# Vin_Buck_Module.net
KiCad netlist of a schematic drawn in EAGLE
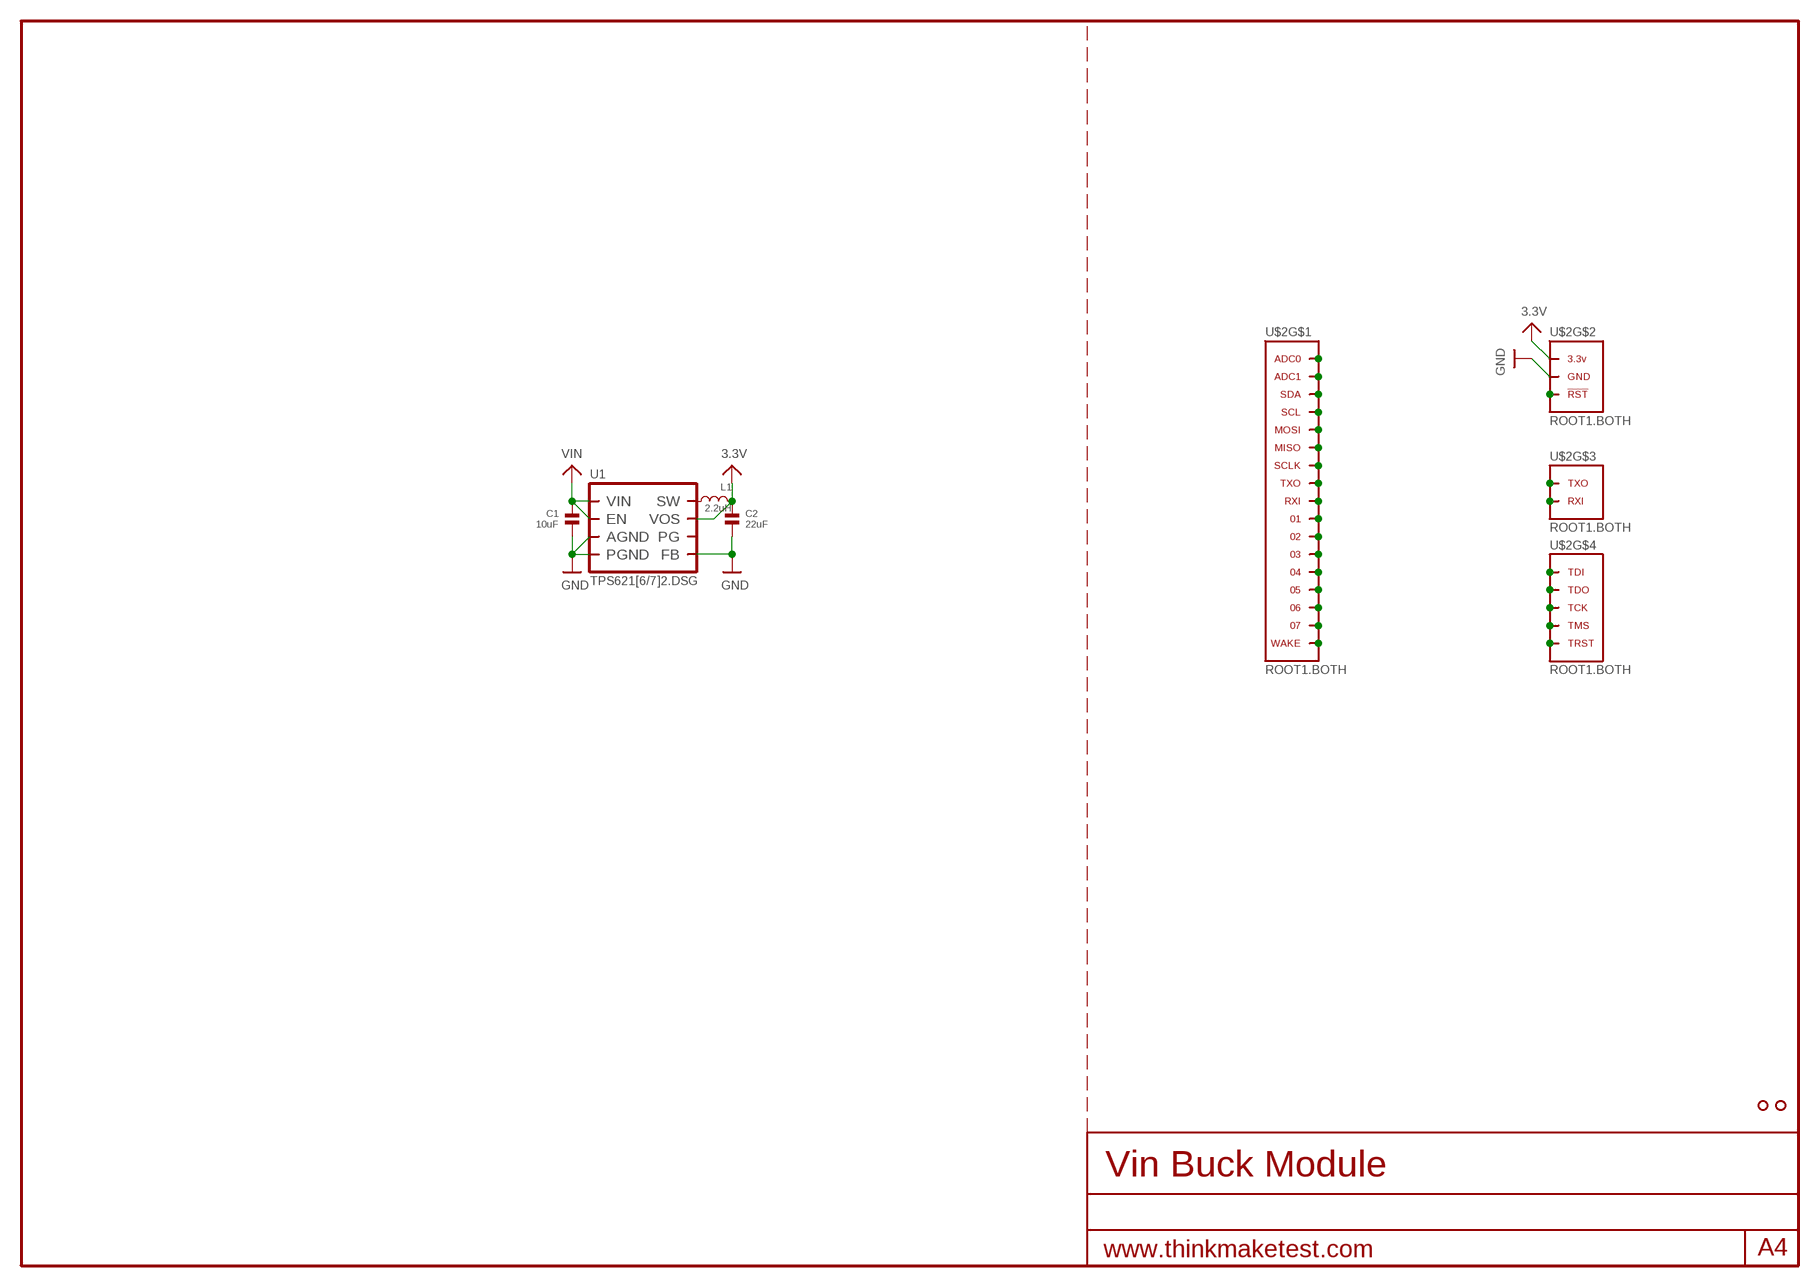
[diagram p0: schematic, sheet 1]

(export (version "E")
  (design (tool "Eeschema 10.0.6"))
  (components
    (comp (ref "C1")
      (value "10uF")
      (footprint "eagle-import:0805")
      (libsource (lib "eagle-import") (part "CAPACITOR.0805"))
    )
    (comp (ref "C2")
      (value "22uF")
      (footprint "eagle-import:0805")
      (libsource (lib "eagle-import") (part "CAPACITOR.0805"))
    )
    (comp (ref "L1")
      (value "2.2uH")
      (footprint "eagle-import:SDR0403")
      (libsource (lib "eagle-import") (part "INDUCTOR-SDR0403"))
    )
    (comp (ref "U$2")
      (value "ROOT1.BOTH")
      (footprint "eagle-import:ROOT1.BOTH")
      (libsource (lib "eagle-import") (part "ROOT1.BOTH"))
    )
    (comp (ref "U$3")
      (value "HOLE.#2")
      (footprint "eagle-import:#2")
      (libsource (lib "eagle-import") (part "HOLE.#2"))
    )
    (comp (ref "U$4")
      (value "HOLE.#2")
      (footprint "eagle-import:#2")
      (libsource (lib "eagle-import") (part "HOLE.#2"))
    )
    (comp (ref "U1")
      (value "TPS621[6/7]2.DSG")
      (footprint "eagle-import:DSG")
      (libsource (lib "eagle-import") (part "TPS621[6/7]2.DSG"))
    )
  )
  (nets
    (net (code "1") (name "3.3V") (class "Default")
      (node (ref "C2") (pin "1") (pinfunction "1_1") (pintype "bidirectional"))
      (node (ref "L1") (pin "1") (pinfunction "1_1") (pintype "passive"))
      (node (ref "U$2") (pin "3.3V@1") (pinfunction "3.3V_3.3V@1") (pintype "bidirectional"))
      (node (ref "U$2") (pin "3.3V@10") (pinfunction "3.3V_3.3V@10") (pintype "bidirectional"))
      (node (ref "U$2") (pin "3.3V@11") (pinfunction "3.3V_3.3V@11") (pintype "bidirectional"))
      (node (ref "U$2") (pin "3.3V@12") (pinfunction "3.3V_3.3V@12") (pintype "bidirectional"))
      (node (ref "U$2") (pin "3.3V@13") (pinfunction "3.3V_3.3V@13") (pintype "bidirectional"))
      (node (ref "U$2") (pin "3.3V@14") (pinfunction "3.3V_3.3V@14") (pintype "bidirectional"))
      (node (ref "U$2") (pin "3.3V@15") (pinfunction "3.3V_3.3V@15") (pintype "bidirectional"))
      (node (ref "U$2") (pin "3.3V@16") (pinfunction "3.3V_3.3V@16") (pintype "bidirectional"))
      (node (ref "U$2") (pin "3.3V@17") (pinfunction "3.3V_3.3V@17") (pintype "bidirectional"))
      (node (ref "U$2") (pin "3.3V@18") (pinfunction "3.3V_3.3V@18") (pintype "bidirectional"))
      (node (ref "U$2") (pin "3.3V@19") (pinfunction "3.3V_3.3V@19") (pintype "bidirectional"))
      (node (ref "U$2") (pin "3.3V@2") (pinfunction "3.3V_3.3V@2") (pintype "bidirectional"))
      (node (ref "U$2") (pin "3.3V@20") (pinfunction "3.3V_3.3V@20") (pintype "bidirectional"))
      (node (ref "U$2") (pin "3.3V@21") (pinfunction "3.3V_3.3V@21") (pintype "bidirectional"))
      (node (ref "U$2") (pin "3.3V@22") (pinfunction "3.3V_3.3V@22") (pintype "bidirectional"))
      (node (ref "U$2") (pin "3.3V@23") (pinfunction "3.3V_3.3V@23") (pintype "bidirectional"))
      (node (ref "U$2") (pin "3.3V@24") (pinfunction "3.3V_3.3V@24") (pintype "bidirectional"))
      (node (ref "U$2") (pin "3.3V@3") (pinfunction "3.3V_3.3V@3") (pintype "bidirectional"))
      (node (ref "U$2") (pin "3.3V@4") (pinfunction "3.3V_3.3V@4") (pintype "bidirectional"))
      (node (ref "U$2") (pin "3.3V@5") (pinfunction "3.3V_3.3V@5") (pintype "bidirectional"))
      (node (ref "U$2") (pin "3.3V@6") (pinfunction "3.3V_3.3V@6") (pintype "bidirectional"))
      (node (ref "U$2") (pin "3.3V@7") (pinfunction "3.3V_3.3V@7") (pintype "bidirectional"))
      (node (ref "U$2") (pin "3.3V@8") (pinfunction "3.3V_3.3V@8") (pintype "bidirectional"))
      (node (ref "U$2") (pin "3.3V@9") (pinfunction "3.3V_3.3V@9") (pintype "bidirectional"))
      (node (ref "U$2") (pin "3.3V@VIA") (pinfunction "3.3V_3.3V@VIA") (pintype "bidirectional"))
      (node (ref "U1") (pin "6") (pinfunction "VOS_6") (pintype "bidirectional"))
    )
    (net (code "2") (name "GND") (class "Default")
      (node (ref "C1") (pin "2") (pinfunction "2_2") (pintype "bidirectional"))
      (node (ref "C2") (pin "2") (pinfunction "2_2") (pintype "bidirectional"))
      (node (ref "U$2") (pin "GND@1") (pinfunction "GND_GND@1") (pintype "bidirectional"))
      (node (ref "U$2") (pin "GND@10") (pinfunction "GND_GND@10") (pintype "bidirectional"))
      (node (ref "U$2") (pin "GND@11") (pinfunction "GND_GND@11") (pintype "bidirectional"))
      (node (ref "U$2") (pin "GND@12") (pinfunction "GND_GND@12") (pintype "bidirectional"))
      (node (ref "U$2") (pin "GND@13") (pinfunction "GND_GND@13") (pintype "bidirectional"))
      (node (ref "U$2") (pin "GND@14") (pinfunction "GND_GND@14") (pintype "bidirectional"))
      (node (ref "U$2") (pin "GND@15") (pinfunction "GND_GND@15") (pintype "bidirectional"))
      (node (ref "U$2") (pin "GND@16") (pinfunction "GND_GND@16") (pintype "bidirectional"))
      (node (ref "U$2") (pin "GND@17") (pinfunction "GND_GND@17") (pintype "bidirectional"))
      (node (ref "U$2") (pin "GND@18") (pinfunction "GND_GND@18") (pintype "bidirectional"))
      (node (ref "U$2") (pin "GND@19") (pinfunction "GND_GND@19") (pintype "bidirectional"))
      (node (ref "U$2") (pin "GND@2") (pinfunction "GND_GND@2") (pintype "bidirectional"))
      (node (ref "U$2") (pin "GND@20") (pinfunction "GND_GND@20") (pintype "bidirectional"))
      (node (ref "U$2") (pin "GND@21") (pinfunction "GND_GND@21") (pintype "bidirectional"))
      (node (ref "U$2") (pin "GND@22") (pinfunction "GND_GND@22") (pintype "bidirectional"))
      (node (ref "U$2") (pin "GND@23") (pinfunction "GND_GND@23") (pintype "bidirectional"))
      (node (ref "U$2") (pin "GND@24") (pinfunction "GND_GND@24") (pintype "bidirectional"))
      (node (ref "U$2") (pin "GND@25") (pinfunction "GND_GND@25") (pintype "bidirectional"))
      (node (ref "U$2") (pin "GND@26") (pinfunction "GND_GND@26") (pintype "bidirectional"))
      (node (ref "U$2") (pin "GND@3") (pinfunction "GND_GND@3") (pintype "bidirectional"))
      (node (ref "U$2") (pin "GND@4") (pinfunction "GND_GND@4") (pintype "bidirectional"))
      (node (ref "U$2") (pin "GND@5") (pinfunction "GND_GND@5") (pintype "bidirectional"))
      (node (ref "U$2") (pin "GND@6") (pinfunction "GND_GND@6") (pintype "bidirectional"))
      (node (ref "U$2") (pin "GND@7") (pinfunction "GND_GND@7") (pintype "bidirectional"))
      (node (ref "U$2") (pin "GND@8") (pinfunction "GND_GND@8") (pintype "bidirectional"))
      (node (ref "U$2") (pin "GND@9") (pinfunction "GND_GND@9") (pintype "bidirectional"))
      (node (ref "U$2") (pin "GND@VIA") (pinfunction "GND_GND@VIA") (pintype "bidirectional"))
      (node (ref "U1") (pin "1") (pinfunction "PGND_1") (pintype "bidirectional"))
      (node (ref "U1") (pin "4") (pinfunction "AGND_4") (pintype "bidirectional"))
      (node (ref "U1") (pin "5") (pinfunction "FB_5") (pintype "bidirectional"))
      (node (ref "U1") (pin "PAD") (pinfunction "AGND_PAD") (pintype "bidirectional"))
    )
    (net (code "3") (name "Net-(U$2-Pad01)") (class "Default")
      (node (ref "U$2") (pin "01") (pinfunction "01_01") (pintype "bidirectional"))
      (node (ref "U$2") (pin "01@1") (pinfunction "01_01@1") (pintype "bidirectional"))
      (node (ref "U$2") (pin "01@VIA") (pinfunction "01_01@VIA") (pintype "bidirectional"))
    )
    (net (code "4") (name "Net-(U$2-Pad02)") (class "Default")
      (node (ref "U$2") (pin "02") (pinfunction "02_02") (pintype "bidirectional"))
      (node (ref "U$2") (pin "02@1") (pinfunction "02_02@1") (pintype "bidirectional"))
      (node (ref "U$2") (pin "02@VIA") (pinfunction "02_02@VIA") (pintype "bidirectional"))
    )
    (net (code "5") (name "Net-(U$2-Pad03)") (class "Default")
      (node (ref "U$2") (pin "03") (pinfunction "03_03") (pintype "bidirectional"))
      (node (ref "U$2") (pin "03@1") (pinfunction "03_03@1") (pintype "bidirectional"))
      (node (ref "U$2") (pin "03@VIA") (pinfunction "03_03@VIA") (pintype "bidirectional"))
    )
    (net (code "6") (name "Net-(U$2-Pad04)") (class "Default")
      (node (ref "U$2") (pin "04") (pinfunction "04_04") (pintype "bidirectional"))
      (node (ref "U$2") (pin "04@1") (pinfunction "04_04@1") (pintype "bidirectional"))
      (node (ref "U$2") (pin "04@VIA") (pinfunction "04_04@VIA") (pintype "bidirectional"))
    )
    (net (code "7") (name "Net-(U$2-Pad05)") (class "Default")
      (node (ref "U$2") (pin "05") (pinfunction "05_05") (pintype "bidirectional"))
      (node (ref "U$2") (pin "05@1") (pinfunction "05_05@1") (pintype "bidirectional"))
      (node (ref "U$2") (pin "05@VIA") (pinfunction "05_05@VIA") (pintype "bidirectional"))
    )
    (net (code "8") (name "Net-(U$2-Pad06)") (class "Default")
      (node (ref "U$2") (pin "06") (pinfunction "06_06") (pintype "bidirectional"))
      (node (ref "U$2") (pin "06@1") (pinfunction "06_06@1") (pintype "bidirectional"))
      (node (ref "U$2") (pin "06@VIA") (pinfunction "06_06@VIA") (pintype "bidirectional"))
    )
    (net (code "9") (name "Net-(U$2-Pad07)") (class "Default")
      (node (ref "U$2") (pin "07") (pinfunction "07_07") (pintype "bidirectional"))
      (node (ref "U$2") (pin "07@1") (pinfunction "07_07@1") (pintype "bidirectional"))
      (node (ref "U$2") (pin "07@VIA") (pinfunction "07_07@VIA") (pintype "bidirectional"))
    )
    (net (code "10") (name "Net-(U$2-PadADC0)") (class "Default")
      (node (ref "U$2") (pin "ADC0") (pinfunction "ADC0_ADC0") (pintype "bidirectional"))
      (node (ref "U$2") (pin "ADC0@1") (pinfunction "ADC0_ADC0@1") (pintype "bidirectional"))
      (node (ref "U$2") (pin "ADC0@VIA") (pinfunction "ADC0_ADC0@VIA") (pintype "bidirectional"))
    )
    (net (code "11") (name "Net-(U$2-PadADC1)") (class "Default")
      (node (ref "U$2") (pin "ADC1") (pinfunction "ADC1_ADC1") (pintype "bidirectional"))
      (node (ref "U$2") (pin "ADC1@1") (pinfunction "ADC1_ADC1@1") (pintype "bidirectional"))
      (node (ref "U$2") (pin "ADC1@VIA") (pinfunction "ADC1_ADC1@VIA") (pintype "bidirectional"))
    )
    (net (code "12") (name "Net-(U$2-PadMISO)") (class "Default")
      (node (ref "U$2") (pin "MISO") (pinfunction "MISO_MISO") (pintype "bidirectional"))
      (node (ref "U$2") (pin "MISO@1") (pinfunction "MISO_MISO@1") (pintype "bidirectional"))
      (node (ref "U$2") (pin "MISO@VIA") (pinfunction "MISO_MISO@VIA") (pintype "bidirectional"))
    )
    (net (code "13") (name "Net-(U$2-PadMOSI)") (class "Default")
      (node (ref "U$2") (pin "MOSI") (pinfunction "MOSI_MOSI") (pintype "bidirectional"))
      (node (ref "U$2") (pin "MOSI@1") (pinfunction "MOSI_MOSI@1") (pintype "bidirectional"))
      (node (ref "U$2") (pin "MOSI@VIA") (pinfunction "MOSI_MOSI@VIA") (pintype "bidirectional"))
    )
    (net (code "14") (name "Net-(U$2-PadRXI)") (class "Default")
      (node (ref "U$2") (pin "RXI") (pinfunction "RXI_RXI") (pintype "bidirectional"))
      (node (ref "U$2") (pin "RXI@1") (pinfunction "RXI_RXI@1") (pintype "bidirectional"))
      (node (ref "U$2") (pin "RXI@VIA") (pinfunction "RXI_RXI@VIA") (pintype "bidirectional"))
    )
    (net (code "15") (name "Net-(U$2-PadSCL)") (class "Default")
      (node (ref "U$2") (pin "SCL") (pinfunction "SCL_SCL") (pintype "bidirectional"))
      (node (ref "U$2") (pin "SCL@1") (pinfunction "SCL_SCL@1") (pintype "bidirectional"))
      (node (ref "U$2") (pin "SCL@VIA") (pinfunction "SCL_SCL@VIA") (pintype "bidirectional"))
    )
    (net (code "16") (name "Net-(U$2-PadSCLK)") (class "Default")
      (node (ref "U$2") (pin "SCLK") (pinfunction "SCLK_SCLK") (pintype "bidirectional"))
      (node (ref "U$2") (pin "SCLK@1") (pinfunction "SCLK_SCLK@1") (pintype "bidirectional"))
      (node (ref "U$2") (pin "SCLK@VIA") (pinfunction "SCLK_SCLK@VIA") (pintype "bidirectional"))
    )
    (net (code "17") (name "Net-(U$2-PadSDA)") (class "Default")
      (node (ref "U$2") (pin "SDA") (pinfunction "SDA_SDA") (pintype "bidirectional"))
      (node (ref "U$2") (pin "SDA@1") (pinfunction "SDA_SDA@1") (pintype "bidirectional"))
      (node (ref "U$2") (pin "SDA@VIA") (pinfunction "SDA_SDA@VIA") (pintype "bidirectional"))
    )
    (net (code "18") (name "Net-(U$2-PadTCK)") (class "Default")
      (node (ref "U$2") (pin "TCK") (pinfunction "TCK_TCK") (pintype "bidirectional"))
      (node (ref "U$2") (pin "TCK@1") (pinfunction "TCK_TCK@1") (pintype "bidirectional"))
      (node (ref "U$2") (pin "TCK@VIA") (pinfunction "TCK_TCK@VIA") (pintype "bidirectional"))
    )
    (net (code "19") (name "Net-(U$2-PadTDI)") (class "Default")
      (node (ref "U$2") (pin "TDI") (pinfunction "TDI_TDI") (pintype "bidirectional"))
      (node (ref "U$2") (pin "TDI@1") (pinfunction "TDI_TDI@1") (pintype "bidirectional"))
      (node (ref "U$2") (pin "TDI@VIA") (pinfunction "TDI_TDI@VIA") (pintype "bidirectional"))
    )
    (net (code "20") (name "Net-(U$2-PadTDO)") (class "Default")
      (node (ref "U$2") (pin "TDO") (pinfunction "TDO_TDO") (pintype "bidirectional"))
      (node (ref "U$2") (pin "TDO@1") (pinfunction "TDO_TDO@1") (pintype "bidirectional"))
      (node (ref "U$2") (pin "TDO@VIA") (pinfunction "TDO_TDO@VIA") (pintype "bidirectional"))
    )
    (net (code "21") (name "Net-(U$2-PadTMS)") (class "Default")
      (node (ref "U$2") (pin "TMS") (pinfunction "TMS_TMS") (pintype "bidirectional"))
      (node (ref "U$2") (pin "TMS@1") (pinfunction "TMS_TMS@1") (pintype "bidirectional"))
      (node (ref "U$2") (pin "TMS@VIA") (pinfunction "TMS_TMS@VIA") (pintype "bidirectional"))
    )
    (net (code "22") (name "Net-(U$2-PadTRST)") (class "Default")
      (node (ref "U$2") (pin "TRST") (pinfunction "TRST_TRST") (pintype "bidirectional"))
      (node (ref "U$2") (pin "TRST@1") (pinfunction "TRST_TRST@1") (pintype "bidirectional"))
      (node (ref "U$2") (pin "TRST@VIA") (pinfunction "TRST_TRST@VIA") (pintype "bidirectional"))
    )
    (net (code "23") (name "Net-(U$2-PadTXO)") (class "Default")
      (node (ref "U$2") (pin "TXO") (pinfunction "TXO_TXO") (pintype "bidirectional"))
      (node (ref "U$2") (pin "TXO@1") (pinfunction "TXO_TXO@1") (pintype "bidirectional"))
      (node (ref "U$2") (pin "TXO@VIA") (pinfunction "TXO_TXO@VIA") (pintype "bidirectional"))
    )
    (net (code "24") (name "Net-(U$2-PadWAKE)") (class "Default")
      (node (ref "U$2") (pin "WAKE") (pinfunction "WAKE_WAKE") (pintype "bidirectional"))
      (node (ref "U$2") (pin "WAKE@1") (pinfunction "WAKE_WAKE@1") (pintype "bidirectional"))
      (node (ref "U$2") (pin "WAKE@VIA") (pinfunction "WAKE_WAKE@VIA") (pintype "bidirectional"))
    )
    (net (code "25") (name "Net-(U$2B-~{RST}-PadRST)") (class "Default")
      (node (ref "U$2") (pin "RST") (pinfunction "~{RST}_RST") (pintype "bidirectional"))
      (node (ref "U$2") (pin "RST@1") (pinfunction "~{RST}_RST@1") (pintype "bidirectional"))
      (node (ref "U$2") (pin "RST@VIA") (pinfunction "~{RST}_RST@VIA") (pintype "bidirectional"))
    )
    (net (code "26") (name "Net-(U$2C-RXI-PadRXI.DBG)") (class "Default")
      (node (ref "U$2") (pin "RXI.DBG") (pinfunction "RXI_RXI.DBG") (pintype "bidirectional"))
      (node (ref "U$2") (pin "RXI.DBG@1") (pinfunction "RXI_RXI.DBG@1") (pintype "bidirectional"))
      (node (ref "U$2") (pin "RXI.DBG@VIA") (pinfunction "RXI_RXI.DBG@VIA") (pintype "bidirectional"))
    )
    (net (code "27") (name "Net-(U$2C-TXO-PadTXO.DBG)") (class "Default")
      (node (ref "U$2") (pin "TXO.DBG") (pinfunction "TXO_TXO.DBG") (pintype "bidirectional"))
      (node (ref "U$2") (pin "TXO.DBG@1") (pinfunction "TXO_TXO.DBG@1") (pintype "bidirectional"))
      (node (ref "U$2") (pin "TXO.DBG@VIA") (pinfunction "TXO_TXO.DBG@VIA") (pintype "bidirectional"))
    )
    (net (code "28") (name "Net-(U1-SW)") (class "Default")
      (node (ref "L1") (pin "2") (pinfunction "2_2") (pintype "passive"))
      (node (ref "U1") (pin "7") (pinfunction "SW_7") (pintype "bidirectional"))
    )
    (net (code "29") (name "VIN") (class "Default")
      (node (ref "C1") (pin "1") (pinfunction "1_1") (pintype "bidirectional"))
      (node (ref "U1") (pin "2") (pinfunction "VIN_2") (pintype "bidirectional"))
      (node (ref "U1") (pin "3") (pinfunction "EN_3") (pintype "bidirectional"))
    )
    (net (code "30") (name "unconnected-(U1-PG-Pad8)") (class "Default")
      (node (ref "U1") (pin "8") (pinfunction "PG_8") (pintype "bidirectional"))
    )
  )
)
